# multiplication.net
KiCad netlist of a schematic drawn in EAGLE
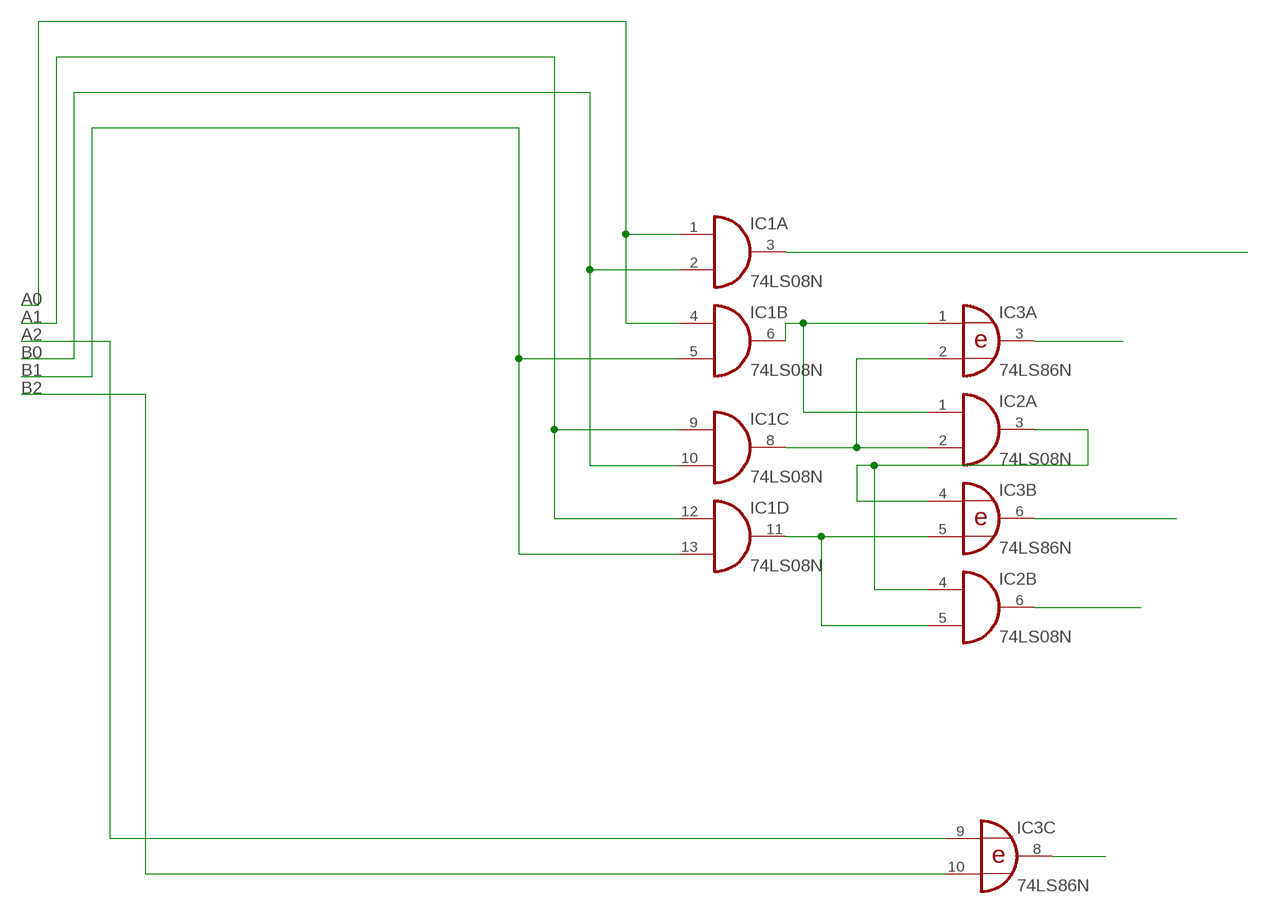
[diagram p0: schematic, sheet 1]

(export (version "E")
  (design (tool "Eeschema 10.0.6"))
  (components
    (comp (ref "IC1")
      (value "74LS08N")
      (footprint "eagle-import:DIL14")
      (libsource (lib "eagle-import") (part "7408NLS"))
    )
    (comp (ref "IC2")
      (value "74LS08N")
      (footprint "eagle-import:DIL14")
      (libsource (lib "eagle-import") (part "7408NLS"))
    )
    (comp (ref "IC3")
      (value "74LS86N")
      (footprint "eagle-import:DIL14")
      (libsource (lib "eagle-import") (part "7486NLS"))
    )
  )
  (nets
    (net (code "1") (name "/A0") (class "Default")
      (node (ref "IC1") (pin "1") (pinfunction "I0_1") (pintype "input"))
      (node (ref "IC1") (pin "4") (pinfunction "I0_4") (pintype "input"))
    )
    (net (code "2") (name "/A1") (class "Default")
      (node (ref "IC1") (pin "12") (pinfunction "I0_12") (pintype "input"))
      (node (ref "IC1") (pin "9") (pinfunction "I0_9") (pintype "input"))
    )
    (net (code "3") (name "/A2") (class "Default")
      (node (ref "IC3") (pin "9") (pinfunction "I0_9") (pintype "input"))
    )
    (net (code "4") (name "/B0") (class "Default")
      (node (ref "IC1") (pin "10") (pinfunction "I1_10") (pintype "input"))
      (node (ref "IC1") (pin "2") (pinfunction "I1_2") (pintype "input"))
    )
    (net (code "5") (name "/B1") (class "Default")
      (node (ref "IC1") (pin "13") (pinfunction "I1_13") (pintype "input"))
      (node (ref "IC1") (pin "5") (pinfunction "I1_5") (pintype "input"))
    )
    (net (code "6") (name "/B2") (class "Default")
      (node (ref "IC3") (pin "10") (pinfunction "I1_10") (pintype "input"))
    )
    (net (code "7") (name "Net-(IC1B-O)") (class "Default")
      (node (ref "IC1") (pin "6") (pinfunction "O_6") (pintype "output"))
      (node (ref "IC2") (pin "1") (pinfunction "I0_1") (pintype "input"))
      (node (ref "IC3") (pin "1") (pinfunction "I0_1") (pintype "input"))
    )
    (net (code "8") (name "Net-(IC1C-O)") (class "Default")
      (node (ref "IC1") (pin "8") (pinfunction "O_8") (pintype "output"))
      (node (ref "IC2") (pin "2") (pinfunction "I1_2") (pintype "input"))
      (node (ref "IC3") (pin "2") (pinfunction "I1_2") (pintype "input"))
    )
    (net (code "9") (name "Net-(IC1D-O)") (class "Default")
      (node (ref "IC1") (pin "11") (pinfunction "O_11") (pintype "output"))
      (node (ref "IC2") (pin "5") (pinfunction "I1_5") (pintype "input"))
      (node (ref "IC3") (pin "5") (pinfunction "I1_5") (pintype "input"))
    )
    (net (code "10") (name "Net-(IC2A-O)") (class "Default")
      (node (ref "IC2") (pin "3") (pinfunction "O_3") (pintype "output"))
      (node (ref "IC2") (pin "4") (pinfunction "I0_4") (pintype "input"))
      (node (ref "IC3") (pin "4") (pinfunction "I0_4") (pintype "input"))
    )
    (net (code "11") (name "unconnected-(IC1A-O-Pad3)") (class "Default")
      (node (ref "IC1") (pin "3") (pinfunction "O_3") (pintype "output"))
    )
    (net (code "12") (name "unconnected-(IC2B-O-Pad6)") (class "Default")
      (node (ref "IC2") (pin "6") (pinfunction "O_6") (pintype "output"))
    )
    (net (code "13") (name "unconnected-(IC3A-O-Pad3)") (class "Default")
      (node (ref "IC3") (pin "3") (pinfunction "O_3") (pintype "output"))
    )
    (net (code "14") (name "unconnected-(IC3B-O-Pad6)") (class "Default")
      (node (ref "IC3") (pin "6") (pinfunction "O_6") (pintype "output"))
    )
    (net (code "15") (name "unconnected-(IC3C-O-Pad8)") (class "Default")
      (node (ref "IC3") (pin "8") (pinfunction "O_8") (pintype "output"))
    )
  )
)
